# Light_Cube.net
KiCad netlist of a schematic drawn in EAGLE
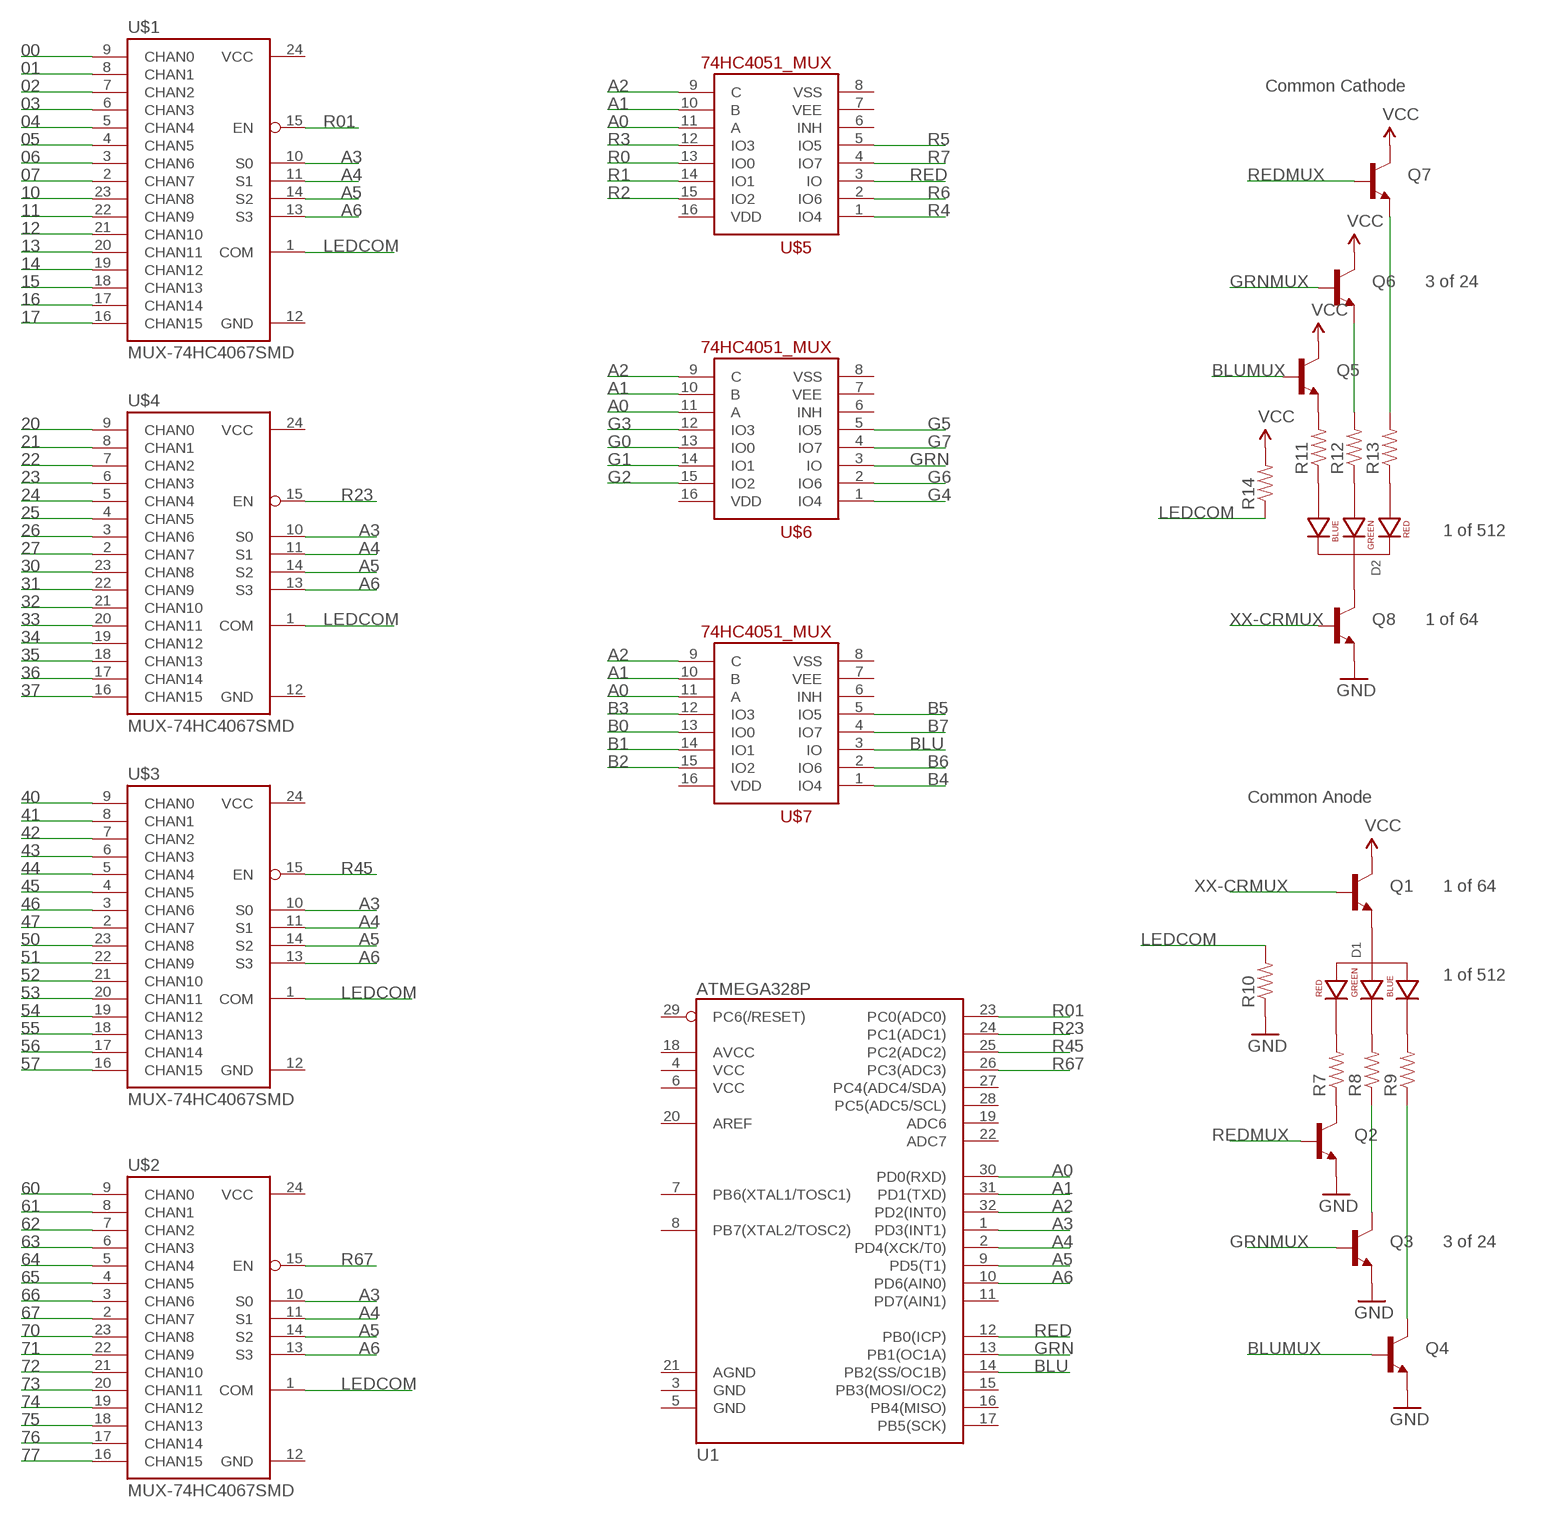
[diagram p0: schematic, sheet 1]

(export (version "E")
  (design (tool "Eeschema 10.0.6"))
  (components
    (comp (ref "D1")
      (value "LED-RGB-CA-THRUCLEAR")
      (footprint "eagle-import:LED-RGB-THRU")
      (libsource (lib "eagle-import") (part "LED-RGB-CA-THRUCLEAR"))
    )
    (comp (ref "D2")
      (value "LED-RGB-CC-THRUCLEAR")
      (footprint "eagle-import:LED-RGB-THRU")
      (libsource (lib "eagle-import") (part "LED-RGB-CC-THRUCLEAR"))
    )
    (comp (ref "Q1")
      (value "TRANSISTOR_NPNTO92")
      (footprint "eagle-import:TO-92")
      (libsource (lib "eagle-import") (part "TRANSISTOR_NPNTO92"))
    )
    (comp (ref "Q2")
      (value "TRANSISTOR_NPNTO92")
      (footprint "eagle-import:TO-92")
      (libsource (lib "eagle-import") (part "TRANSISTOR_NPNTO92"))
    )
    (comp (ref "Q3")
      (value "TRANSISTOR_NPNTO92")
      (footprint "eagle-import:TO-92")
      (libsource (lib "eagle-import") (part "TRANSISTOR_NPNTO92"))
    )
    (comp (ref "Q4")
      (value "TRANSISTOR_NPNTO92")
      (footprint "eagle-import:TO-92")
      (libsource (lib "eagle-import") (part "TRANSISTOR_NPNTO92"))
    )
    (comp (ref "Q5")
      (value "TRANSISTOR_NPNTO92")
      (footprint "eagle-import:TO-92")
      (libsource (lib "eagle-import") (part "TRANSISTOR_NPNTO92"))
    )
    (comp (ref "Q6")
      (value "TRANSISTOR_NPNTO92")
      (footprint "eagle-import:TO-92")
      (libsource (lib "eagle-import") (part "TRANSISTOR_NPNTO92"))
    )
    (comp (ref "Q7")
      (value "TRANSISTOR_NPNTO92")
      (footprint "eagle-import:TO-92")
      (libsource (lib "eagle-import") (part "TRANSISTOR_NPNTO92"))
    )
    (comp (ref "Q8")
      (value "TRANSISTOR_NPNTO92")
      (footprint "eagle-import:TO-92")
      (libsource (lib "eagle-import") (part "TRANSISTOR_NPNTO92"))
    )
    (comp (ref "R7")
      (value "RESISTORPTH-1/4W")
      (footprint "eagle-import:AXIAL-0.4")
      (libsource (lib "eagle-import") (part "RESISTORPTH-1/4W"))
    )
    (comp (ref "R8")
      (value "RESISTORPTH-1/4W")
      (footprint "eagle-import:AXIAL-0.4")
      (libsource (lib "eagle-import") (part "RESISTORPTH-1/4W"))
    )
    (comp (ref "R9")
      (value "RESISTORPTH-1/4W")
      (footprint "eagle-import:AXIAL-0.4")
      (libsource (lib "eagle-import") (part "RESISTORPTH-1/4W"))
    )
    (comp (ref "R10")
      (value "RESISTORPTH-1/4W")
      (footprint "eagle-import:AXIAL-0.4")
      (libsource (lib "eagle-import") (part "RESISTORPTH-1/4W"))
    )
    (comp (ref "R11")
      (value "RESISTORPTH-1/4W")
      (footprint "eagle-import:AXIAL-0.4")
      (libsource (lib "eagle-import") (part "RESISTORPTH-1/4W"))
    )
    (comp (ref "R12")
      (value "RESISTORPTH-1/4W")
      (footprint "eagle-import:AXIAL-0.4")
      (libsource (lib "eagle-import") (part "RESISTORPTH-1/4W"))
    )
    (comp (ref "R13")
      (value "RESISTORPTH-1/4W")
      (footprint "eagle-import:AXIAL-0.4")
      (libsource (lib "eagle-import") (part "RESISTORPTH-1/4W"))
    )
    (comp (ref "R14")
      (value "RESISTORPTH-1/4W")
      (footprint "eagle-import:AXIAL-0.4")
      (libsource (lib "eagle-import") (part "RESISTORPTH-1/4W"))
    )
    (comp (ref "U$1")
      (value "MUX-74HC4067SMD")
      (footprint "eagle-import:SSOP24")
      (libsource (lib "eagle-import") (part "MUX-74HC4067SMD"))
    )
    (comp (ref "U$2")
      (value "MUX-74HC4067SMD")
      (footprint "eagle-import:SSOP24")
      (libsource (lib "eagle-import") (part "MUX-74HC4067SMD"))
    )
    (comp (ref "U$3")
      (value "MUX-74HC4067SMD")
      (footprint "eagle-import:SSOP24")
      (libsource (lib "eagle-import") (part "MUX-74HC4067SMD"))
    )
    (comp (ref "U$4")
      (value "MUX-74HC4067SMD")
      (footprint "eagle-import:SSOP24")
      (libsource (lib "eagle-import") (part "MUX-74HC4067SMD"))
    )
    (comp (ref "U$5")
      (value "74HC4051_MUX")
      (footprint "eagle-import:SO16")
      (libsource (lib "eagle-import") (part "74HC4051_MUX"))
    )
    (comp (ref "U$6")
      (value "74HC4051_MUX")
      (footprint "eagle-import:SO16")
      (libsource (lib "eagle-import") (part "74HC4051_MUX"))
    )
    (comp (ref "U$7")
      (value "74HC4051_MUX")
      (footprint "eagle-import:SO16")
      (libsource (lib "eagle-import") (part "74HC4051_MUX"))
    )
    (comp (ref "U1")
      (value "ATMEGA328P")
      (footprint "eagle-import:TQFP32-08")
      (libsource (lib "eagle-import") (part "ATMEGA328_SMT"))
    )
  )
  (nets
    (net (code "1") (name "/00") (class "Default")
      (node (ref "U$1") (pin "9") (pinfunction "CHAN0_9") (pintype "bidirectional"))
    )
    (net (code "2") (name "/01") (class "Default")
      (node (ref "U$1") (pin "8") (pinfunction "CHAN1_8") (pintype "bidirectional"))
    )
    (net (code "3") (name "/02") (class "Default")
      (node (ref "U$1") (pin "7") (pinfunction "CHAN2_7") (pintype "bidirectional"))
    )
    (net (code "4") (name "/03") (class "Default")
      (node (ref "U$1") (pin "6") (pinfunction "CHAN3_6") (pintype "bidirectional"))
    )
    (net (code "5") (name "/04") (class "Default")
      (node (ref "U$1") (pin "5") (pinfunction "CHAN4_5") (pintype "bidirectional"))
    )
    (net (code "6") (name "/05") (class "Default")
      (node (ref "U$1") (pin "4") (pinfunction "CHAN5_4") (pintype "bidirectional"))
    )
    (net (code "7") (name "/06") (class "Default")
      (node (ref "U$1") (pin "3") (pinfunction "CHAN6_3") (pintype "bidirectional"))
    )
    (net (code "8") (name "/07") (class "Default")
      (node (ref "U$1") (pin "2") (pinfunction "CHAN7_2") (pintype "bidirectional"))
    )
    (net (code "9") (name "/10") (class "Default")
      (node (ref "U$1") (pin "23") (pinfunction "CHAN8_23") (pintype "bidirectional"))
    )
    (net (code "10") (name "/11") (class "Default")
      (node (ref "U$1") (pin "22") (pinfunction "CHAN9_22") (pintype "bidirectional"))
    )
    (net (code "11") (name "/12") (class "Default")
      (node (ref "U$1") (pin "21") (pinfunction "CHAN10_21") (pintype "bidirectional"))
    )
    (net (code "12") (name "/13") (class "Default")
      (node (ref "U$1") (pin "20") (pinfunction "CHAN11_20") (pintype "bidirectional"))
    )
    (net (code "13") (name "/14") (class "Default")
      (node (ref "U$1") (pin "19") (pinfunction "CHAN12_19") (pintype "bidirectional"))
    )
    (net (code "14") (name "/15") (class "Default")
      (node (ref "U$1") (pin "18") (pinfunction "CHAN13_18") (pintype "bidirectional"))
    )
    (net (code "15") (name "/16") (class "Default")
      (node (ref "U$1") (pin "17") (pinfunction "CHAN14_17") (pintype "bidirectional"))
    )
    (net (code "16") (name "/17") (class "Default")
      (node (ref "U$1") (pin "16") (pinfunction "CHAN15_16") (pintype "bidirectional"))
    )
    (net (code "17") (name "/20") (class "Default")
      (node (ref "U$4") (pin "9") (pinfunction "CHAN0_9") (pintype "bidirectional"))
    )
    (net (code "18") (name "/21") (class "Default")
      (node (ref "U$4") (pin "8") (pinfunction "CHAN1_8") (pintype "bidirectional"))
    )
    (net (code "19") (name "/22") (class "Default")
      (node (ref "U$4") (pin "7") (pinfunction "CHAN2_7") (pintype "bidirectional"))
    )
    (net (code "20") (name "/23") (class "Default")
      (node (ref "U$4") (pin "6") (pinfunction "CHAN3_6") (pintype "bidirectional"))
    )
    (net (code "21") (name "/24") (class "Default")
      (node (ref "U$4") (pin "5") (pinfunction "CHAN4_5") (pintype "bidirectional"))
    )
    (net (code "22") (name "/25") (class "Default")
      (node (ref "U$4") (pin "4") (pinfunction "CHAN5_4") (pintype "bidirectional"))
    )
    (net (code "23") (name "/26") (class "Default")
      (node (ref "U$4") (pin "3") (pinfunction "CHAN6_3") (pintype "bidirectional"))
    )
    (net (code "24") (name "/27") (class "Default")
      (node (ref "U$4") (pin "2") (pinfunction "CHAN7_2") (pintype "bidirectional"))
    )
    (net (code "25") (name "/30") (class "Default")
      (node (ref "U$4") (pin "23") (pinfunction "CHAN8_23") (pintype "bidirectional"))
    )
    (net (code "26") (name "/31") (class "Default")
      (node (ref "U$4") (pin "22") (pinfunction "CHAN9_22") (pintype "bidirectional"))
    )
    (net (code "27") (name "/32") (class "Default")
      (node (ref "U$4") (pin "21") (pinfunction "CHAN10_21") (pintype "bidirectional"))
    )
    (net (code "28") (name "/33") (class "Default")
      (node (ref "U$4") (pin "20") (pinfunction "CHAN11_20") (pintype "bidirectional"))
    )
    (net (code "29") (name "/34") (class "Default")
      (node (ref "U$4") (pin "19") (pinfunction "CHAN12_19") (pintype "bidirectional"))
    )
    (net (code "30") (name "/35") (class "Default")
      (node (ref "U$4") (pin "18") (pinfunction "CHAN13_18") (pintype "bidirectional"))
    )
    (net (code "31") (name "/36") (class "Default")
      (node (ref "U$4") (pin "17") (pinfunction "CHAN14_17") (pintype "bidirectional"))
    )
    (net (code "32") (name "/37") (class "Default")
      (node (ref "U$4") (pin "16") (pinfunction "CHAN15_16") (pintype "bidirectional"))
    )
    (net (code "33") (name "/40") (class "Default")
      (node (ref "U$3") (pin "9") (pinfunction "CHAN0_9") (pintype "bidirectional"))
    )
    (net (code "34") (name "/41") (class "Default")
      (node (ref "U$3") (pin "8") (pinfunction "CHAN1_8") (pintype "bidirectional"))
    )
    (net (code "35") (name "/42") (class "Default")
      (node (ref "U$3") (pin "7") (pinfunction "CHAN2_7") (pintype "bidirectional"))
    )
    (net (code "36") (name "/43") (class "Default")
      (node (ref "U$3") (pin "6") (pinfunction "CHAN3_6") (pintype "bidirectional"))
    )
    (net (code "37") (name "/44") (class "Default")
      (node (ref "U$3") (pin "5") (pinfunction "CHAN4_5") (pintype "bidirectional"))
    )
    (net (code "38") (name "/45") (class "Default")
      (node (ref "U$3") (pin "4") (pinfunction "CHAN5_4") (pintype "bidirectional"))
    )
    (net (code "39") (name "/46") (class "Default")
      (node (ref "U$3") (pin "3") (pinfunction "CHAN6_3") (pintype "bidirectional"))
    )
    (net (code "40") (name "/47") (class "Default")
      (node (ref "U$3") (pin "2") (pinfunction "CHAN7_2") (pintype "bidirectional"))
    )
    (net (code "41") (name "/50") (class "Default")
      (node (ref "U$3") (pin "23") (pinfunction "CHAN8_23") (pintype "bidirectional"))
    )
    (net (code "42") (name "/51") (class "Default")
      (node (ref "U$3") (pin "22") (pinfunction "CHAN9_22") (pintype "bidirectional"))
    )
    (net (code "43") (name "/52") (class "Default")
      (node (ref "U$3") (pin "21") (pinfunction "CHAN10_21") (pintype "bidirectional"))
    )
    (net (code "44") (name "/53") (class "Default")
      (node (ref "U$3") (pin "20") (pinfunction "CHAN11_20") (pintype "bidirectional"))
    )
    (net (code "45") (name "/54") (class "Default")
      (node (ref "U$3") (pin "19") (pinfunction "CHAN12_19") (pintype "bidirectional"))
    )
    (net (code "46") (name "/55") (class "Default")
      (node (ref "U$3") (pin "18") (pinfunction "CHAN13_18") (pintype "bidirectional"))
    )
    (net (code "47") (name "/56") (class "Default")
      (node (ref "U$3") (pin "17") (pinfunction "CHAN14_17") (pintype "bidirectional"))
    )
    (net (code "48") (name "/57") (class "Default")
      (node (ref "U$3") (pin "16") (pinfunction "CHAN15_16") (pintype "bidirectional"))
    )
    (net (code "49") (name "/60") (class "Default")
      (node (ref "U$2") (pin "9") (pinfunction "CHAN0_9") (pintype "bidirectional"))
    )
    (net (code "50") (name "/61") (class "Default")
      (node (ref "U$2") (pin "8") (pinfunction "CHAN1_8") (pintype "bidirectional"))
    )
    (net (code "51") (name "/62") (class "Default")
      (node (ref "U$2") (pin "7") (pinfunction "CHAN2_7") (pintype "bidirectional"))
    )
    (net (code "52") (name "/63") (class "Default")
      (node (ref "U$2") (pin "6") (pinfunction "CHAN3_6") (pintype "bidirectional"))
    )
    (net (code "53") (name "/64") (class "Default")
      (node (ref "U$2") (pin "5") (pinfunction "CHAN4_5") (pintype "bidirectional"))
    )
    (net (code "54") (name "/65") (class "Default")
      (node (ref "U$2") (pin "4") (pinfunction "CHAN5_4") (pintype "bidirectional"))
    )
    (net (code "55") (name "/66") (class "Default")
      (node (ref "U$2") (pin "3") (pinfunction "CHAN6_3") (pintype "bidirectional"))
    )
    (net (code "56") (name "/67") (class "Default")
      (node (ref "U$2") (pin "2") (pinfunction "CHAN7_2") (pintype "bidirectional"))
    )
    (net (code "57") (name "/70") (class "Default")
      (node (ref "U$2") (pin "23") (pinfunction "CHAN8_23") (pintype "bidirectional"))
    )
    (net (code "58") (name "/71") (class "Default")
      (node (ref "U$2") (pin "22") (pinfunction "CHAN9_22") (pintype "bidirectional"))
    )
    (net (code "59") (name "/72") (class "Default")
      (node (ref "U$2") (pin "21") (pinfunction "CHAN10_21") (pintype "bidirectional"))
    )
    (net (code "60") (name "/73") (class "Default")
      (node (ref "U$2") (pin "20") (pinfunction "CHAN11_20") (pintype "bidirectional"))
    )
    (net (code "61") (name "/74") (class "Default")
      (node (ref "U$2") (pin "19") (pinfunction "CHAN12_19") (pintype "bidirectional"))
    )
    (net (code "62") (name "/75") (class "Default")
      (node (ref "U$2") (pin "18") (pinfunction "CHAN13_18") (pintype "bidirectional"))
    )
    (net (code "63") (name "/76") (class "Default")
      (node (ref "U$2") (pin "17") (pinfunction "CHAN14_17") (pintype "bidirectional"))
    )
    (net (code "64") (name "/77") (class "Default")
      (node (ref "U$2") (pin "16") (pinfunction "CHAN15_16") (pintype "bidirectional"))
    )
    (net (code "65") (name "/A0") (class "Default")
      (node (ref "U$5") (pin "11") (pinfunction "A_11") (pintype "bidirectional"))
      (node (ref "U$6") (pin "11") (pinfunction "A_11") (pintype "bidirectional"))
      (node (ref "U$7") (pin "11") (pinfunction "A_11") (pintype "bidirectional"))
      (node (ref "U1") (pin "30") (pinfunction "PD0(RXD)_30") (pintype "bidirectional"))
    )
    (net (code "66") (name "/A1") (class "Default")
      (node (ref "U$5") (pin "10") (pinfunction "B_10") (pintype "bidirectional"))
      (node (ref "U$6") (pin "10") (pinfunction "B_10") (pintype "bidirectional"))
      (node (ref "U$7") (pin "10") (pinfunction "B_10") (pintype "bidirectional"))
      (node (ref "U1") (pin "31") (pinfunction "PD1(TXD)_31") (pintype "bidirectional"))
    )
    (net (code "67") (name "/A2") (class "Default")
      (node (ref "U$5") (pin "9") (pinfunction "C_9") (pintype "bidirectional"))
      (node (ref "U$6") (pin "9") (pinfunction "C_9") (pintype "bidirectional"))
      (node (ref "U$7") (pin "9") (pinfunction "C_9") (pintype "bidirectional"))
      (node (ref "U1") (pin "32") (pinfunction "PD2(INT0)_32") (pintype "bidirectional"))
    )
    (net (code "68") (name "/A3") (class "Default")
      (node (ref "U$1") (pin "10") (pinfunction "S0_10") (pintype "input"))
      (node (ref "U$2") (pin "10") (pinfunction "S0_10") (pintype "input"))
      (node (ref "U$3") (pin "10") (pinfunction "S0_10") (pintype "input"))
      (node (ref "U$4") (pin "10") (pinfunction "S0_10") (pintype "input"))
      (node (ref "U1") (pin "1") (pinfunction "PD3(INT1)_1") (pintype "bidirectional"))
    )
    (net (code "69") (name "/A4") (class "Default")
      (node (ref "U$1") (pin "11") (pinfunction "S1_11") (pintype "input"))
      (node (ref "U$2") (pin "11") (pinfunction "S1_11") (pintype "input"))
      (node (ref "U$3") (pin "11") (pinfunction "S1_11") (pintype "input"))
      (node (ref "U$4") (pin "11") (pinfunction "S1_11") (pintype "input"))
      (node (ref "U1") (pin "2") (pinfunction "PD4(XCK/T0)_2") (pintype "bidirectional"))
    )
    (net (code "70") (name "/A5") (class "Default")
      (node (ref "U$1") (pin "14") (pinfunction "S2_14") (pintype "input"))
      (node (ref "U$2") (pin "14") (pinfunction "S2_14") (pintype "input"))
      (node (ref "U$3") (pin "14") (pinfunction "S2_14") (pintype "input"))
      (node (ref "U$4") (pin "14") (pinfunction "S2_14") (pintype "input"))
      (node (ref "U1") (pin "9") (pinfunction "PD5(T1)_9") (pintype "bidirectional"))
    )
    (net (code "71") (name "/A6") (class "Default")
      (node (ref "U$1") (pin "13") (pinfunction "S3_13") (pintype "input"))
      (node (ref "U$2") (pin "13") (pinfunction "S3_13") (pintype "input"))
      (node (ref "U$3") (pin "13") (pinfunction "S3_13") (pintype "input"))
      (node (ref "U$4") (pin "13") (pinfunction "S3_13") (pintype "input"))
      (node (ref "U1") (pin "10") (pinfunction "PD6(AIN0)_10") (pintype "bidirectional"))
    )
    (net (code "72") (name "/B0") (class "Default")
      (node (ref "U$7") (pin "13") (pinfunction "IO0_13") (pintype "bidirectional"))
    )
    (net (code "73") (name "/B1") (class "Default")
      (node (ref "U$7") (pin "14") (pinfunction "IO1_14") (pintype "bidirectional"))
    )
    (net (code "74") (name "/B2") (class "Default")
      (node (ref "U$7") (pin "15") (pinfunction "IO2_15") (pintype "bidirectional"))
    )
    (net (code "75") (name "/B3") (class "Default")
      (node (ref "U$7") (pin "12") (pinfunction "IO3_12") (pintype "bidirectional"))
    )
    (net (code "76") (name "/B4") (class "Default")
      (node (ref "U$7") (pin "1") (pinfunction "IO4_1") (pintype "bidirectional"))
    )
    (net (code "77") (name "/B5") (class "Default")
      (node (ref "U$7") (pin "5") (pinfunction "IO5_5") (pintype "bidirectional"))
    )
    (net (code "78") (name "/B6") (class "Default")
      (node (ref "U$7") (pin "2") (pinfunction "IO6_2") (pintype "bidirectional"))
    )
    (net (code "79") (name "/B7") (class "Default")
      (node (ref "U$7") (pin "4") (pinfunction "IO7_4") (pintype "bidirectional"))
    )
    (net (code "80") (name "/BLU") (class "Default")
      (node (ref "U$7") (pin "3") (pinfunction "IO_3") (pintype "bidirectional"))
      (node (ref "U1") (pin "14") (pinfunction "PB2(SS/OC1B)_14") (pintype "bidirectional"))
    )
    (net (code "81") (name "/BLUMUX") (class "Default")
      (node (ref "Q4") (pin "2") (pinfunction "B_2") (pintype "passive"))
      (node (ref "Q5") (pin "2") (pinfunction "B_2") (pintype "passive"))
    )
    (net (code "82") (name "/G0") (class "Default")
      (node (ref "U$6") (pin "13") (pinfunction "IO0_13") (pintype "bidirectional"))
    )
    (net (code "83") (name "/G1") (class "Default")
      (node (ref "U$6") (pin "14") (pinfunction "IO1_14") (pintype "bidirectional"))
    )
    (net (code "84") (name "/G2") (class "Default")
      (node (ref "U$6") (pin "15") (pinfunction "IO2_15") (pintype "bidirectional"))
    )
    (net (code "85") (name "/G3") (class "Default")
      (node (ref "U$6") (pin "12") (pinfunction "IO3_12") (pintype "bidirectional"))
    )
    (net (code "86") (name "/G4") (class "Default")
      (node (ref "U$6") (pin "1") (pinfunction "IO4_1") (pintype "bidirectional"))
    )
    (net (code "87") (name "/G5") (class "Default")
      (node (ref "U$6") (pin "5") (pinfunction "IO5_5") (pintype "bidirectional"))
    )
    (net (code "88") (name "/G6") (class "Default")
      (node (ref "U$6") (pin "2") (pinfunction "IO6_2") (pintype "bidirectional"))
    )
    (net (code "89") (name "/G7") (class "Default")
      (node (ref "U$6") (pin "4") (pinfunction "IO7_4") (pintype "bidirectional"))
    )
    (net (code "90") (name "/GRN") (class "Default")
      (node (ref "U$6") (pin "3") (pinfunction "IO_3") (pintype "bidirectional"))
      (node (ref "U1") (pin "13") (pinfunction "PB1(OC1A)_13") (pintype "bidirectional"))
    )
    (net (code "91") (name "/GRNMUX") (class "Default")
      (node (ref "Q3") (pin "2") (pinfunction "B_2") (pintype "passive"))
      (node (ref "Q6") (pin "2") (pinfunction "B_2") (pintype "passive"))
    )
    (net (code "92") (name "/LEDCOM") (class "Default")
      (node (ref "R10") (pin "P$2") (pinfunction "2_P$2") (pintype "passive"))
      (node (ref "R14") (pin "P$1") (pinfunction "1_P$1") (pintype "passive"))
      (node (ref "U$1") (pin "1") (pinfunction "COM_1") (pintype "bidirectional"))
      (node (ref "U$2") (pin "1") (pinfunction "COM_1") (pintype "bidirectional"))
      (node (ref "U$3") (pin "1") (pinfunction "COM_1") (pintype "bidirectional"))
      (node (ref "U$4") (pin "1") (pinfunction "COM_1") (pintype "bidirectional"))
    )
    (net (code "93") (name "/R0") (class "Default")
      (node (ref "U$5") (pin "13") (pinfunction "IO0_13") (pintype "bidirectional"))
    )
    (net (code "94") (name "/R01") (class "Default")
      (node (ref "U$1") (pin "15") (pinfunction "EN_15") (pintype "input"))
      (node (ref "U1") (pin "23") (pinfunction "PC0(ADC0)_23") (pintype "bidirectional"))
    )
    (net (code "95") (name "/R1") (class "Default")
      (node (ref "U$5") (pin "14") (pinfunction "IO1_14") (pintype "bidirectional"))
    )
    (net (code "96") (name "/R2") (class "Default")
      (node (ref "U$5") (pin "15") (pinfunction "IO2_15") (pintype "bidirectional"))
    )
    (net (code "97") (name "/R3") (class "Default")
      (node (ref "U$5") (pin "12") (pinfunction "IO3_12") (pintype "bidirectional"))
    )
    (net (code "98") (name "/R4") (class "Default")
      (node (ref "U$5") (pin "1") (pinfunction "IO4_1") (pintype "bidirectional"))
    )
    (net (code "99") (name "/R5") (class "Default")
      (node (ref "U$5") (pin "5") (pinfunction "IO5_5") (pintype "bidirectional"))
    )
    (net (code "100") (name "/R6") (class "Default")
      (node (ref "U$5") (pin "2") (pinfunction "IO6_2") (pintype "bidirectional"))
    )
    (net (code "101") (name "/R7") (class "Default")
      (node (ref "U$5") (pin "4") (pinfunction "IO7_4") (pintype "bidirectional"))
    )
    (net (code "102") (name "/R23") (class "Default")
      (node (ref "U$4") (pin "15") (pinfunction "EN_15") (pintype "input"))
      (node (ref "U1") (pin "24") (pinfunction "PC1(ADC1)_24") (pintype "bidirectional"))
    )
    (net (code "103") (name "/R45") (class "Default")
      (node (ref "U$3") (pin "15") (pinfunction "EN_15") (pintype "input"))
      (node (ref "U1") (pin "25") (pinfunction "PC2(ADC2)_25") (pintype "bidirectional"))
    )
    (net (code "104") (name "/R67") (class "Default")
      (node (ref "U$2") (pin "15") (pinfunction "EN_15") (pintype "input"))
      (node (ref "U1") (pin "26") (pinfunction "PC3(ADC3)_26") (pintype "bidirectional"))
    )
    (net (code "105") (name "/RED") (class "Default")
      (node (ref "U$5") (pin "3") (pinfunction "IO_3") (pintype "bidirectional"))
      (node (ref "U1") (pin "12") (pinfunction "PB0(ICP)_12") (pintype "bidirectional"))
    )
    (net (code "106") (name "/REDMUX") (class "Default")
      (node (ref "Q2") (pin "2") (pinfunction "B_2") (pintype "passive"))
      (node (ref "Q7") (pin "2") (pinfunction "B_2") (pintype "passive"))
    )
    (net (code "107") (name "/XX-CRMUX") (class "Default")
      (node (ref "Q1") (pin "2") (pinfunction "B_2") (pintype "passive"))
      (node (ref "Q8") (pin "2") (pinfunction "B_2") (pintype "passive"))
    )
    (net (code "108") (name "GND") (class "Default")
      (node (ref "Q2") (pin "1") (pinfunction "E_1") (pintype "passive"))
      (node (ref "Q3") (pin "1") (pinfunction "E_1") (pintype "passive"))
      (node (ref "Q4") (pin "1") (pinfunction "E_1") (pintype "passive"))
      (node (ref "Q8") (pin "1") (pinfunction "E_1") (pintype "passive"))
      (node (ref "R10") (pin "P$1") (pinfunction "1_P$1") (pintype "passive"))
    )
    (net (code "109") (name "Net-(D1-ANODE)") (class "Default")
      (node (ref "D1") (pin "2") (pinfunction "ANODE_2") (pintype "bidirectional"))
      (node (ref "Q1") (pin "1") (pinfunction "E_1") (pintype "passive"))
    )
    (net (code "110") (name "Net-(D1-BLUE_CATHODE)") (class "Default")
      (node (ref "D1") (pin "4") (pinfunction "BLUE_CATHODE_4") (pintype "bidirectional"))
      (node (ref "R9") (pin "P$2") (pinfunction "2_P$2") (pintype "passive"))
    )
    (net (code "111") (name "Net-(D1-GREEN_CATHODE)") (class "Default")
      (node (ref "D1") (pin "3") (pinfunction "GREEN_CATHODE_3") (pintype "bidirectional"))
      (node (ref "R8") (pin "P$2") (pinfunction "2_P$2") (pintype "passive"))
    )
    (net (code "112") (name "Net-(D1-RED_CATHODE)") (class "Default")
      (node (ref "D1") (pin "1") (pinfunction "RED_CATHODE_1") (pintype "bidirectional"))
      (node (ref "R7") (pin "P$2") (pinfunction "2_P$2") (pintype "passive"))
    )
    (net (code "113") (name "Net-(D2-BLUE_CATHODE)") (class "Default")
      (node (ref "D2") (pin "4") (pinfunction "BLUE_CATHODE_4") (pintype "bidirectional"))
      (node (ref "R11") (pin "P$1") (pinfunction "1_P$1") (pintype "passive"))
    )
    (net (code "114") (name "Net-(D2-CATHODE)") (class "Default")
      (node (ref "D2") (pin "2") (pinfunction "CATHODE_2") (pintype "bidirectional"))
      (node (ref "Q8") (pin "3") (pinfunction "C_3") (pintype "passive"))
    )
    (net (code "115") (name "Net-(D2-GREEN_CATHODE)") (class "Default")
      (node (ref "D2") (pin "3") (pinfunction "GREEN_CATHODE_3") (pintype "bidirectional"))
      (node (ref "R12") (pin "P$1") (pinfunction "1_P$1") (pintype "passive"))
    )
    (net (code "116") (name "Net-(D2-RED_CATHODE)") (class "Default")
      (node (ref "D2") (pin "1") (pinfunction "RED_CATHODE_1") (pintype "bidirectional"))
      (node (ref "R13") (pin "P$1") (pinfunction "1_P$1") (pintype "passive"))
    )
    (net (code "117") (name "Net-(Q2-C)") (class "Default")
      (node (ref "Q2") (pin "3") (pinfunction "C_3") (pintype "passive"))
      (node (ref "R7") (pin "P$1") (pinfunction "1_P$1") (pintype "passive"))
    )
    (net (code "118") (name "Net-(Q3-C)") (class "Default")
      (node (ref "Q3") (pin "3") (pinfunction "C_3") (pintype "passive"))
      (node (ref "R8") (pin "P$1") (pinfunction "1_P$1") (pintype "passive"))
    )
    (net (code "119") (name "Net-(Q4-C)") (class "Default")
      (node (ref "Q4") (pin "3") (pinfunction "C_3") (pintype "passive"))
      (node (ref "R9") (pin "P$1") (pinfunction "1_P$1") (pintype "passive"))
    )
    (net (code "120") (name "Net-(Q5-E)") (class "Default")
      (node (ref "Q5") (pin "1") (pinfunction "E_1") (pintype "passive"))
      (node (ref "R11") (pin "P$2") (pinfunction "2_P$2") (pintype "passive"))
    )
    (net (code "121") (name "Net-(Q6-E)") (class "Default")
      (node (ref "Q6") (pin "1") (pinfunction "E_1") (pintype "passive"))
      (node (ref "R12") (pin "P$2") (pinfunction "2_P$2") (pintype "passive"))
    )
    (net (code "122") (name "Net-(Q7-E)") (class "Default")
      (node (ref "Q7") (pin "1") (pinfunction "E_1") (pintype "passive"))
      (node (ref "R13") (pin "P$2") (pinfunction "2_P$2") (pintype "passive"))
    )
    (net (code "123") (name "VCC") (class "Default")
      (node (ref "Q1") (pin "3") (pinfunction "C_3") (pintype "passive"))
      (node (ref "Q5") (pin "3") (pinfunction "C_3") (pintype "passive"))
      (node (ref "Q6") (pin "3") (pinfunction "C_3") (pintype "passive"))
      (node (ref "Q7") (pin "3") (pinfunction "C_3") (pintype "passive"))
      (node (ref "R14") (pin "P$2") (pinfunction "2_P$2") (pintype "passive"))
    )
    (net (code "124") (name "unconnected-(U$1-GND-Pad12)") (class "Default")
      (node (ref "U$1") (pin "12") (pinfunction "GND_12") (pintype "bidirectional"))
    )
    (net (code "125") (name "unconnected-(U$1-VCC-Pad24)") (class "Default")
      (node (ref "U$1") (pin "24") (pinfunction "VCC_24") (pintype "bidirectional"))
    )
    (net (code "126") (name "unconnected-(U$2-GND-Pad12)") (class "Default")
      (node (ref "U$2") (pin "12") (pinfunction "GND_12") (pintype "bidirectional"))
    )
    (net (code "127") (name "unconnected-(U$2-VCC-Pad24)") (class "Default")
      (node (ref "U$2") (pin "24") (pinfunction "VCC_24") (pintype "bidirectional"))
    )
    (net (code "128") (name "unconnected-(U$3-GND-Pad12)") (class "Default")
      (node (ref "U$3") (pin "12") (pinfunction "GND_12") (pintype "bidirectional"))
    )
    (net (code "129") (name "unconnected-(U$3-VCC-Pad24)") (class "Default")
      (node (ref "U$3") (pin "24") (pinfunction "VCC_24") (pintype "bidirectional"))
    )
    (net (code "130") (name "unconnected-(U$4-GND-Pad12)") (class "Default")
      (node (ref "U$4") (pin "12") (pinfunction "GND_12") (pintype "bidirectional"))
    )
    (net (code "131") (name "unconnected-(U$4-VCC-Pad24)") (class "Default")
      (node (ref "U$4") (pin "24") (pinfunction "VCC_24") (pintype "bidirectional"))
    )
    (net (code "132") (name "unconnected-(U$5-INH-Pad6)") (class "Default")
      (node (ref "U$5") (pin "6") (pinfunction "INH_6") (pintype "bidirectional"))
    )
    (net (code "133") (name "unconnected-(U$5-VDD-Pad16)") (class "Default")
      (node (ref "U$5") (pin "16") (pinfunction "VDD_16") (pintype "bidirectional"))
    )
    (net (code "134") (name "unconnected-(U$5-VEE-Pad7)") (class "Default")
      (node (ref "U$5") (pin "7") (pinfunction "VEE_7") (pintype "bidirectional"))
    )
    (net (code "135") (name "unconnected-(U$5-VSS-Pad8)") (class "Default")
      (node (ref "U$5") (pin "8") (pinfunction "VSS_8") (pintype "bidirectional"))
    )
    (net (code "136") (name "unconnected-(U$6-INH-Pad6)") (class "Default")
      (node (ref "U$6") (pin "6") (pinfunction "INH_6") (pintype "bidirectional"))
    )
    (net (code "137") (name "unconnected-(U$6-VDD-Pad16)") (class "Default")
      (node (ref "U$6") (pin "16") (pinfunction "VDD_16") (pintype "bidirectional"))
    )
    (net (code "138") (name "unconnected-(U$6-VEE-Pad7)") (class "Default")
      (node (ref "U$6") (pin "7") (pinfunction "VEE_7") (pintype "bidirectional"))
    )
    (net (code "139") (name "unconnected-(U$6-VSS-Pad8)") (class "Default")
      (node (ref "U$6") (pin "8") (pinfunction "VSS_8") (pintype "bidirectional"))
    )
    (net (code "140") (name "unconnected-(U$7-INH-Pad6)") (class "Default")
      (node (ref "U$7") (pin "6") (pinfunction "INH_6") (pintype "bidirectional"))
    )
    (net (code "141") (name "unconnected-(U$7-VDD-Pad16)") (class "Default")
      (node (ref "U$7") (pin "16") (pinfunction "VDD_16") (pintype "bidirectional"))
    )
    (net (code "142") (name "unconnected-(U$7-VEE-Pad7)") (class "Default")
      (node (ref "U$7") (pin "7") (pinfunction "VEE_7") (pintype "bidirectional"))
    )
    (net (code "143") (name "unconnected-(U$7-VSS-Pad8)") (class "Default")
      (node (ref "U$7") (pin "8") (pinfunction "VSS_8") (pintype "bidirectional"))
    )
    (net (code "144") (name "unconnected-(U1-ADC6-Pad19)") (class "Default")
      (node (ref "U1") (pin "19") (pinfunction "ADC6_19") (pintype "bidirectional"))
    )
    (net (code "145") (name "unconnected-(U1-ADC7-Pad22)") (class "Default")
      (node (ref "U1") (pin "22") (pinfunction "ADC7_22") (pintype "bidirectional"))
    )
    (net (code "146") (name "unconnected-(U1-AGND-Pad21)") (class "Default")
      (node (ref "U1") (pin "21") (pinfunction "AGND_21") (pintype "bidirectional"))
    )
    (net (code "147") (name "unconnected-(U1-AREF-Pad20)") (class "Default")
      (node (ref "U1") (pin "20") (pinfunction "AREF_20") (pintype "bidirectional"))
    )
    (net (code "148") (name "unconnected-(U1-AVCC-Pad18)") (class "Default")
      (node (ref "U1") (pin "18") (pinfunction "AVCC_18") (pintype "bidirectional"))
    )
    (net (code "149") (name "unconnected-(U1-GND-Pad3)") (class "Default")
      (node (ref "U1") (pin "3") (pinfunction "GND_3") (pintype "bidirectional"))
    )
    (net (code "150") (name "unconnected-(U1-GND-Pad5)") (class "Default")
      (node (ref "U1") (pin "5") (pinfunction "GND_5") (pintype "bidirectional"))
    )
    (net (code "151") (name "unconnected-(U1-PB3(MOSI{slash}OC2)-Pad15)") (class "Default")
      (node (ref "U1") (pin "15") (pinfunction "PB3(MOSI/OC2)_15") (pintype "bidirectional"))
    )
    (net (code "152") (name "unconnected-(U1-PB4(MISO)-Pad16)") (class "Default")
      (node (ref "U1") (pin "16") (pinfunction "PB4(MISO)_16") (pintype "bidirectional"))
    )
    (net (code "153") (name "unconnected-(U1-PB5(SCK)-Pad17)") (class "Default")
      (node (ref "U1") (pin "17") (pinfunction "PB5(SCK)_17") (pintype "bidirectional"))
    )
    (net (code "154") (name "unconnected-(U1-PB6(XTAL1{slash}TOSC1)-Pad7)") (class "Default")
      (node (ref "U1") (pin "7") (pinfunction "PB6(XTAL1/TOSC1)_7") (pintype "bidirectional"))
    )
    (net (code "155") (name "unconnected-(U1-PB7(XTAL2{slash}TOSC2)-Pad8)") (class "Default")
      (node (ref "U1") (pin "8") (pinfunction "PB7(XTAL2/TOSC2)_8") (pintype "bidirectional"))
    )
    (net (code "156") (name "unconnected-(U1-PC4(ADC4{slash}SDA)-Pad27)") (class "Default")
      (node (ref "U1") (pin "27") (pinfunction "PC4(ADC4/SDA)_27") (pintype "bidirectional"))
    )
    (net (code "157") (name "unconnected-(U1-PC5(ADC5{slash}SCL)-Pad28)") (class "Default")
      (node (ref "U1") (pin "28") (pinfunction "PC5(ADC5/SCL)_28") (pintype "bidirectional"))
    )
    (net (code "158") (name "unconnected-(U1-PC6({slash}RESET)-Pad29)") (class "Default")
      (node (ref "U1") (pin "29") (pinfunction "PC6(/RESET)_29") (pintype "bidirectional"))
    )
    (net (code "159") (name "unconnected-(U1-PD7(AIN1)-Pad11)") (class "Default")
      (node (ref "U1") (pin "11") (pinfunction "PD7(AIN1)_11") (pintype "bidirectional"))
    )
    (net (code "160") (name "unconnected-(U1-VCC-Pad4)") (class "Default")
      (node (ref "U1") (pin "4") (pinfunction "VCC_4") (pintype "bidirectional"))
    )
    (net (code "161") (name "unconnected-(U1-VCC-Pad6)") (class "Default")
      (node (ref "U1") (pin "6") (pinfunction "VCC_6") (pintype "bidirectional"))
    )
  )
)
